# Key_Led.net
KiCad netlist of a schematic drawn in Altium Designer
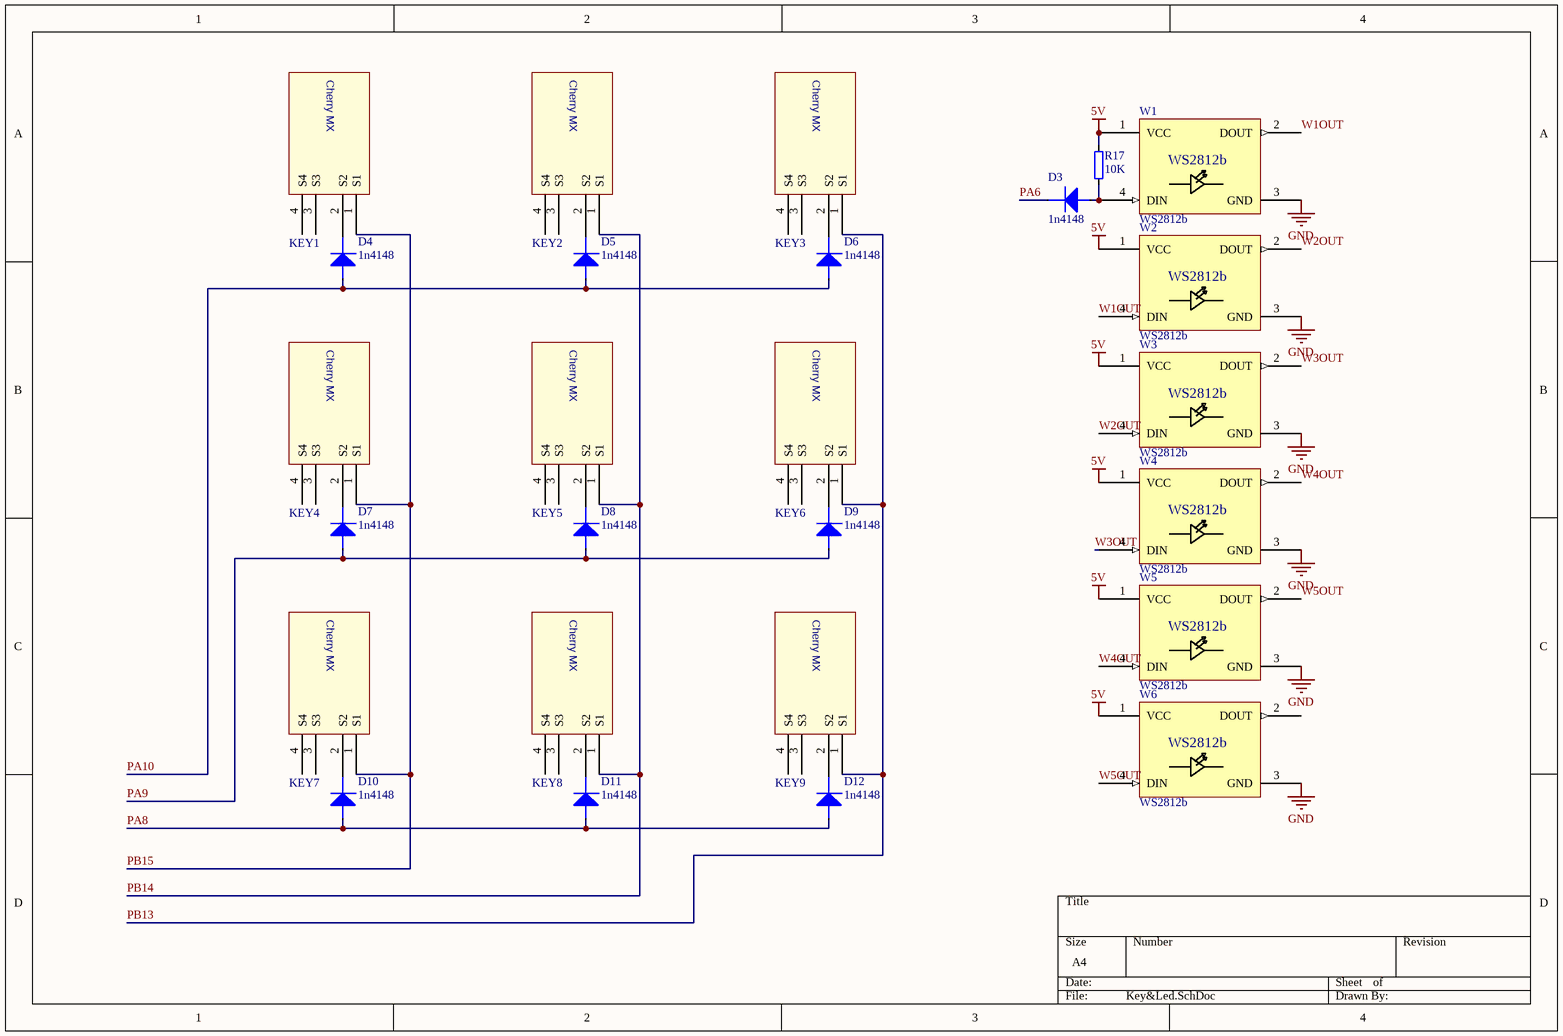
[diagram p0: Key&Led.SchDoc]

(export (version "E")
  (design (tool "Eeschema 10.0.6"))
  (components
    (comp (ref "D3")
      (value "1n4148")
      (footprint "SOD-123")
      (description "Zener Diode")
      (libsource (lib "二极管") (part "ZENER3"))
    )
    (comp (ref "D4")
      (value "1n4148")
      (footprint "SOD-123")
      (description "Zener Diode")
      (libsource (lib "二极管") (part "ZENER3"))
    )
    (comp (ref "D5")
      (value "1n4148")
      (footprint "SOD-123")
      (description "Zener Diode")
      (libsource (lib "二极管") (part "ZENER3"))
    )
    (comp (ref "D6")
      (value "1n4148")
      (footprint "SOD-123")
      (description "Zener Diode")
      (libsource (lib "二极管") (part "ZENER3"))
    )
    (comp (ref "D7")
      (value "1n4148")
      (footprint "SOD-123")
      (description "Zener Diode")
      (libsource (lib "二极管") (part "ZENER3"))
    )
    (comp (ref "D8")
      (value "1n4148")
      (footprint "SOD-123")
      (description "Zener Diode")
      (libsource (lib "二极管") (part "ZENER3"))
    )
    (comp (ref "D9")
      (value "1n4148")
      (footprint "SOD-123")
      (description "Zener Diode")
      (libsource (lib "二极管") (part "ZENER3"))
    )
    (comp (ref "D10")
      (value "1n4148")
      (footprint "SOD-123")
      (description "Zener Diode")
      (libsource (lib "二极管") (part "ZENER3"))
    )
    (comp (ref "D11")
      (value "1n4148")
      (footprint "SOD-123")
      (description "Zener Diode")
      (libsource (lib "二极管") (part "ZENER3"))
    )
    (comp (ref "D12")
      (value "1n4148")
      (footprint "SOD-123")
      (description "Zener Diode")
      (libsource (lib "二极管") (part "ZENER3"))
    )
    (comp (ref "KEY1")
      (value "CHERRY_MX")
      (footprint "CHERRYMX")
      (libsource (lib "Fsociety_Keyboard") (part "CHERRY_MX"))
    )
    (comp (ref "KEY2")
      (value "CHERRY_MX")
      (footprint "CHERRYMX")
      (libsource (lib "Fsociety_Keyboard") (part "CHERRY_MX"))
    )
    (comp (ref "KEY3")
      (value "CHERRY_MX")
      (footprint "CHERRYMX")
      (libsource (lib "Fsociety_Keyboard") (part "CHERRY_MX"))
    )
    (comp (ref "KEY4")
      (value "CHERRY_MX")
      (footprint "CHERRYMX")
      (libsource (lib "Fsociety_Keyboard") (part "CHERRY_MX"))
    )
    (comp (ref "KEY5")
      (value "CHERRY_MX")
      (footprint "CHERRYMX")
      (libsource (lib "Fsociety_Keyboard") (part "CHERRY_MX"))
    )
    (comp (ref "KEY6")
      (value "CHERRY_MX")
      (footprint "CHERRYMX")
      (libsource (lib "Fsociety_Keyboard") (part "CHERRY_MX"))
    )
    (comp (ref "KEY7")
      (value "CHERRY_MX")
      (footprint "CHERRYMX")
      (libsource (lib "Fsociety_Keyboard") (part "CHERRY_MX"))
    )
    (comp (ref "KEY8")
      (value "CHERRY_MX")
      (footprint "CHERRYMX")
      (libsource (lib "Fsociety_Keyboard") (part "CHERRY_MX"))
    )
    (comp (ref "KEY9")
      (value "CHERRY_MX")
      (footprint "CHERRYMX")
      (libsource (lib "Fsociety_Keyboard") (part "CHERRY_MX"))
    )
    (comp (ref "R17") (value "10K") (footprint "R 0603_L") (libsource (lib "电阻") (part "RES")))
    (comp (ref "W1")
      (value "WS2812b")
      (footprint "DIOC500500X250_NR")
      (description "The Infamous Chinese Chainable RGB LED")
      (libsource (lib "Fsociety_Keyboard") (part "WS2812b_Sumasta"))
    )
    (comp (ref "W2")
      (value "WS2812b")
      (footprint "DIOC500500X250_NR")
      (description "The Infamous Chinese Chainable RGB LED")
      (libsource (lib "Fsociety_Keyboard") (part "WS2812b_Sumasta"))
    )
    (comp (ref "W3")
      (value "WS2812b")
      (footprint "DIOC500500X250_NR")
      (description "The Infamous Chinese Chainable RGB LED")
      (libsource (lib "Fsociety_Keyboard") (part "WS2812b_Sumasta"))
    )
    (comp (ref "W4")
      (value "WS2812b")
      (footprint "DIOC500500X250_NR")
      (description "The Infamous Chinese Chainable RGB LED")
      (libsource (lib "Fsociety_Keyboard") (part "WS2812b_Sumasta"))
    )
    (comp (ref "W5")
      (value "WS2812b")
      (footprint "DIOC500500X250_NR")
      (description "The Infamous Chinese Chainable RGB LED")
      (libsource (lib "Fsociety_Keyboard") (part "WS2812b_Sumasta"))
    )
    (comp (ref "W6")
      (value "WS2812b")
      (footprint "DIOC500500X250_NR")
      (description "The Infamous Chinese Chainable RGB LED")
      (libsource (lib "Fsociety_Keyboard") (part "WS2812b_Sumasta"))
    )
  )
  (nets
    (net (code "1") (name "/PA6") (class "Default")
      (node (ref "D3") (pin "2") (pinfunction "K_2") (pintype "passive"))
    )
    (net (code "2") (name "/PA8") (class "Default")
      (node (ref "D10") (pin "1") (pinfunction "A_1") (pintype "passive"))
      (node (ref "D11") (pin "1") (pinfunction "A_1") (pintype "passive"))
      (node (ref "D12") (pin "1") (pinfunction "A_1") (pintype "passive"))
    )
    (net (code "3") (name "/PA9") (class "Default")
      (node (ref "D7") (pin "1") (pinfunction "A_1") (pintype "passive"))
      (node (ref "D8") (pin "1") (pinfunction "A_1") (pintype "passive"))
      (node (ref "D9") (pin "1") (pinfunction "A_1") (pintype "passive"))
    )
    (net (code "4") (name "/PA10") (class "Default")
      (node (ref "D4") (pin "1") (pinfunction "A_1") (pintype "passive"))
      (node (ref "D5") (pin "1") (pinfunction "A_1") (pintype "passive"))
      (node (ref "D6") (pin "1") (pinfunction "A_1") (pintype "passive"))
    )
    (net (code "5") (name "/PB13") (class "Default")
      (node (ref "KEY3") (pin "1") (pinfunction "S1_1") (pintype "passive"))
      (node (ref "KEY6") (pin "1") (pinfunction "S1_1") (pintype "passive"))
      (node (ref "KEY9") (pin "1") (pinfunction "S1_1") (pintype "passive"))
    )
    (net (code "6") (name "/PB14") (class "Default")
      (node (ref "KEY2") (pin "1") (pinfunction "S1_1") (pintype "passive"))
      (node (ref "KEY5") (pin "1") (pinfunction "S1_1") (pintype "passive"))
      (node (ref "KEY8") (pin "1") (pinfunction "S1_1") (pintype "passive"))
    )
    (net (code "7") (name "/PB15") (class "Default")
      (node (ref "KEY1") (pin "1") (pinfunction "S1_1") (pintype "passive"))
      (node (ref "KEY4") (pin "1") (pinfunction "S1_1") (pintype "passive"))
      (node (ref "KEY7") (pin "1") (pinfunction "S1_1") (pintype "passive"))
    )
    (net (code "8") (name "/W1OUT") (class "Default")
      (node (ref "W1") (pin "2") (pinfunction "DOUT_2") (pintype "output"))
      (node (ref "W2") (pin "4") (pinfunction "DIN_4") (pintype "input"))
    )
    (net (code "9") (name "/W2OUT") (class "Default")
      (node (ref "W2") (pin "2") (pinfunction "DOUT_2") (pintype "output"))
      (node (ref "W3") (pin "4") (pinfunction "DIN_4") (pintype "input"))
    )
    (net (code "10") (name "/W3OUT") (class "Default")
      (node (ref "W3") (pin "2") (pinfunction "DOUT_2") (pintype "output"))
      (node (ref "W4") (pin "4") (pinfunction "DIN_4") (pintype "input"))
    )
    (net (code "11") (name "/W4OUT") (class "Default")
      (node (ref "W4") (pin "2") (pinfunction "DOUT_2") (pintype "output"))
      (node (ref "W5") (pin "4") (pinfunction "DIN_4") (pintype "input"))
    )
    (net (code "12") (name "/W5OUT") (class "Default")
      (node (ref "W5") (pin "2") (pinfunction "DOUT_2") (pintype "output"))
      (node (ref "W6") (pin "4") (pinfunction "DIN_4") (pintype "input"))
    )
    (net (code "13") (name "5V") (class "Default")
      (node (ref "R17") (pin "1") (pinfunction "1_1") (pintype "passive"))
      (node (ref "W1") (pin "1") (pinfunction "VCC_1") (pintype "power_in"))
      (node (ref "W2") (pin "1") (pinfunction "VCC_1") (pintype "power_in"))
      (node (ref "W3") (pin "1") (pinfunction "VCC_1") (pintype "power_in"))
      (node (ref "W4") (pin "1") (pinfunction "VCC_1") (pintype "power_in"))
      (node (ref "W5") (pin "1") (pinfunction "VCC_1") (pintype "power_in"))
      (node (ref "W6") (pin "1") (pinfunction "VCC_1") (pintype "power_in"))
    )
    (net (code "14") (name "GND") (class "Default")
      (node (ref "W1") (pin "3") (pinfunction "GND_3") (pintype "power_in"))
      (node (ref "W2") (pin "3") (pinfunction "GND_3") (pintype "power_in"))
      (node (ref "W3") (pin "3") (pinfunction "GND_3") (pintype "power_in"))
      (node (ref "W4") (pin "3") (pinfunction "GND_3") (pintype "power_in"))
      (node (ref "W5") (pin "3") (pinfunction "GND_3") (pintype "power_in"))
      (node (ref "W6") (pin "3") (pinfunction "GND_3") (pintype "power_in"))
    )
    (net (code "15") (name "Net-(D3-A)") (class "Default")
      (node (ref "D3") (pin "1") (pinfunction "A_1") (pintype "passive"))
      (node (ref "R17") (pin "2") (pinfunction "2_2") (pintype "passive"))
      (node (ref "W1") (pin "4") (pinfunction "DIN_4") (pintype "input"))
    )
    (net (code "16") (name "Net-(D4-K)") (class "Default")
      (node (ref "D4") (pin "2") (pinfunction "K_2") (pintype "passive"))
      (node (ref "KEY1") (pin "2") (pinfunction "S2_2") (pintype "passive"))
    )
    (net (code "17") (name "Net-(D5-K)") (class "Default")
      (node (ref "D5") (pin "2") (pinfunction "K_2") (pintype "passive"))
      (node (ref "KEY2") (pin "2") (pinfunction "S2_2") (pintype "passive"))
    )
    (net (code "18") (name "Net-(D6-K)") (class "Default")
      (node (ref "D6") (pin "2") (pinfunction "K_2") (pintype "passive"))
      (node (ref "KEY3") (pin "2") (pinfunction "S2_2") (pintype "passive"))
    )
    (net (code "19") (name "Net-(D7-K)") (class "Default")
      (node (ref "D7") (pin "2") (pinfunction "K_2") (pintype "passive"))
      (node (ref "KEY4") (pin "2") (pinfunction "S2_2") (pintype "passive"))
    )
    (net (code "20") (name "Net-(D8-K)") (class "Default")
      (node (ref "D8") (pin "2") (pinfunction "K_2") (pintype "passive"))
      (node (ref "KEY5") (pin "2") (pinfunction "S2_2") (pintype "passive"))
    )
    (net (code "21") (name "Net-(D9-K)") (class "Default")
      (node (ref "D9") (pin "2") (pinfunction "K_2") (pintype "passive"))
      (node (ref "KEY6") (pin "2") (pinfunction "S2_2") (pintype "passive"))
    )
    (net (code "22") (name "Net-(D10-K)") (class "Default")
      (node (ref "D10") (pin "2") (pinfunction "K_2") (pintype "passive"))
      (node (ref "KEY7") (pin "2") (pinfunction "S2_2") (pintype "passive"))
    )
    (net (code "23") (name "Net-(D11-K)") (class "Default")
      (node (ref "D11") (pin "2") (pinfunction "K_2") (pintype "passive"))
      (node (ref "KEY8") (pin "2") (pinfunction "S2_2") (pintype "passive"))
    )
    (net (code "24") (name "Net-(D12-K)") (class "Default")
      (node (ref "D12") (pin "2") (pinfunction "K_2") (pintype "passive"))
      (node (ref "KEY9") (pin "2") (pinfunction "S2_2") (pintype "passive"))
    )
    (net (code "25") (name "unconnected-(KEY1-S3-Pad3)") (class "Default")
      (node (ref "KEY1") (pin "3") (pinfunction "S3_3") (pintype "passive"))
    )
    (net (code "26") (name "unconnected-(KEY1-S4-Pad4)") (class "Default")
      (node (ref "KEY1") (pin "4") (pinfunction "S4_4") (pintype "passive"))
    )
    (net (code "27") (name "unconnected-(KEY2-S3-Pad3)") (class "Default")
      (node (ref "KEY2") (pin "3") (pinfunction "S3_3") (pintype "passive"))
    )
    (net (code "28") (name "unconnected-(KEY2-S4-Pad4)") (class "Default")
      (node (ref "KEY2") (pin "4") (pinfunction "S4_4") (pintype "passive"))
    )
    (net (code "29") (name "unconnected-(KEY3-S3-Pad3)") (class "Default")
      (node (ref "KEY3") (pin "3") (pinfunction "S3_3") (pintype "passive"))
    )
    (net (code "30") (name "unconnected-(KEY3-S4-Pad4)") (class "Default")
      (node (ref "KEY3") (pin "4") (pinfunction "S4_4") (pintype "passive"))
    )
    (net (code "31") (name "unconnected-(KEY4-S3-Pad3)") (class "Default")
      (node (ref "KEY4") (pin "3") (pinfunction "S3_3") (pintype "passive"))
    )
    (net (code "32") (name "unconnected-(KEY4-S4-Pad4)") (class "Default")
      (node (ref "KEY4") (pin "4") (pinfunction "S4_4") (pintype "passive"))
    )
    (net (code "33") (name "unconnected-(KEY5-S3-Pad3)") (class "Default")
      (node (ref "KEY5") (pin "3") (pinfunction "S3_3") (pintype "passive"))
    )
    (net (code "34") (name "unconnected-(KEY5-S4-Pad4)") (class "Default")
      (node (ref "KEY5") (pin "4") (pinfunction "S4_4") (pintype "passive"))
    )
    (net (code "35") (name "unconnected-(KEY6-S3-Pad3)") (class "Default")
      (node (ref "KEY6") (pin "3") (pinfunction "S3_3") (pintype "passive"))
    )
    (net (code "36") (name "unconnected-(KEY6-S4-Pad4)") (class "Default")
      (node (ref "KEY6") (pin "4") (pinfunction "S4_4") (pintype "passive"))
    )
    (net (code "37") (name "unconnected-(KEY7-S3-Pad3)") (class "Default")
      (node (ref "KEY7") (pin "3") (pinfunction "S3_3") (pintype "passive"))
    )
    (net (code "38") (name "unconnected-(KEY7-S4-Pad4)") (class "Default")
      (node (ref "KEY7") (pin "4") (pinfunction "S4_4") (pintype "passive"))
    )
    (net (code "39") (name "unconnected-(KEY8-S3-Pad3)") (class "Default")
      (node (ref "KEY8") (pin "3") (pinfunction "S3_3") (pintype "passive"))
    )
    (net (code "40") (name "unconnected-(KEY8-S4-Pad4)") (class "Default")
      (node (ref "KEY8") (pin "4") (pinfunction "S4_4") (pintype "passive"))
    )
    (net (code "41") (name "unconnected-(KEY9-S3-Pad3)") (class "Default")
      (node (ref "KEY9") (pin "3") (pinfunction "S3_3") (pintype "passive"))
    )
    (net (code "42") (name "unconnected-(KEY9-S4-Pad4)") (class "Default")
      (node (ref "KEY9") (pin "4") (pinfunction "S4_4") (pintype "passive"))
    )
    (net (code "43") (name "unconnected-(W6-DOUT-Pad2)") (class "Default")
      (node (ref "W6") (pin "2") (pinfunction "DOUT_2") (pintype "output"))
    )
  )
)
